# power_supply.net
KiCad netlist of a schematic drawn in EAGLE
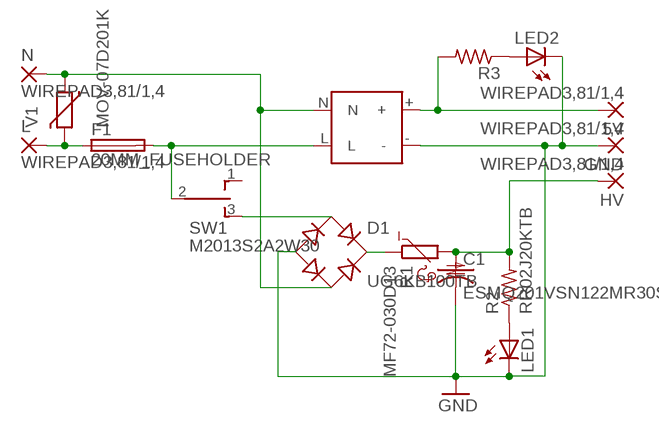
[diagram p0: schematic, sheet 1]

(export (version "E")
  (design (tool "Eeschema 10.0.6"))
  (components
    (comp (ref "5V")
      (value "WIREPAD3,81/1,4")
      (footprint "eagle-import:3,81_1,4")
      (libsource (lib "eagle-import") (part "WIREPAD3,81/1,4"))
    )
    (comp (ref "C1")
      (value "ESMQ201VSN122MR30S")
      (footprint "eagle-import:CAPPRD1000W200D3000H3000B")
      (libsource (lib "eagle-import") (part "ESMQ201VSN122MR30S"))
    )
    (comp (ref "D1")
      (value "UG6KB100TB")
      (footprint "eagle-import:UG6KB100TB")
      (libsource (lib "eagle-import") (part "UG6KB100TB"))
    )
    (comp (ref "F1")
      (value "20MM_FUSEHOLDER")
      (footprint "eagle-import:20MM_FUSEHOLDER")
      (libsource (lib "eagle-import") (part "20MM_FUSEHOLDER"))
    )
    (comp (ref "GND")
      (value "WIREPAD3,81/1,4")
      (footprint "eagle-import:3,81_1,4")
      (libsource (lib "eagle-import") (part "WIREPAD3,81/1,4"))
    )
    (comp (ref "HV")
      (value "WIREPAD3,81/1,4")
      (footprint "eagle-import:3,81_1,4")
      (libsource (lib "eagle-import") (part "WIREPAD3,81/1,4"))
    )
    (comp (ref "L")
      (value "WIREPAD3,81/1,4")
      (footprint "eagle-import:3,81_1,4")
      (libsource (lib "eagle-import") (part "WIREPAD3,81/1,4"))
    )
    (comp (ref "LED1")
      (value "LED5MM")
      (footprint "eagle-import:LED5MM")
      (libsource (lib "eagle-import") (part "LED5MM"))
    )
    (comp (ref "LED2")
      (value "LED5MM")
      (footprint "eagle-import:LED5MM")
      (libsource (lib "eagle-import") (part "LED5MM"))
    )
    (comp (ref "M1")
      (value "IRM-15-5")
      (footprint "eagle-import:IRM-15-5")
      (libsource (lib "eagle-import") (part "IRM-15-5"))
    )
    (comp (ref "N")
      (value "WIREPAD3,81/1,4")
      (footprint "eagle-import:3,81_1,4")
      (libsource (lib "eagle-import") (part "WIREPAD3,81/1,4"))
    )
    (comp (ref "R1")
      (value "MF72-030D13")
      (footprint "eagle-import:MF72-030D13")
      (libsource (lib "eagle-import") (part "MF72-030D13"))
    )
    (comp (ref "R2")
      (value "RR02J20KTB")
      (footprint "eagle-import:RESAD1360W80L900D350B")
      (libsource (lib "eagle-import") (part "RR02J20KTB"))
    )
    (comp (ref "R3")
      (value "R-US_0207/10")
      (footprint "eagle-import:0207_10")
      (libsource (lib "eagle-import") (part "R-US_0207/10"))
    )
    (comp (ref "SW1")
      (value "M2013S2A2W30")
      (footprint "eagle-import:M2013S2A2W30")
      (libsource (lib "eagle-import") (part "M2013S2A2W30"))
    )
    (comp (ref "V1")
      (value "MOV-07D201K")
      (footprint "eagle-import:MOV-07D201K")
      (libsource (lib "eagle-import") (part "MOV-07D201K"))
    )
  )
  (nets
    (net (code "1") (name "GND") (class "Default")
      (node (ref "C1") (pin "-") (pinfunction "2_-") (pintype "passive"))
      (node (ref "D1") (pin "-") (pinfunction "-_-") (pintype "passive"))
      (node (ref "GND") (pin "1") (pinfunction "P_1") (pintype "passive"))
      (node (ref "LED1") (pin "K") (pinfunction "C_K") (pintype "passive"))
      (node (ref "LED2") (pin "K") (pinfunction "C_K") (pintype "passive"))
      (node (ref "M1") (pin "-") (pinfunction "-_-") (pintype "bidirectional"))
    )
    (net (code "2") (name "Net-(5V-P)") (class "Default")
      (node (ref "5V") (pin "1") (pinfunction "P_1") (pintype "passive"))
      (node (ref "M1") (pin "+") (pinfunction "+_+") (pintype "bidirectional"))
      (node (ref "R3") (pin "2") (pinfunction "2_2") (pintype "passive"))
    )
    (net (code "3") (name "Net-(C1-1)") (class "Default")
      (node (ref "C1") (pin "+") (pinfunction "1_+") (pintype "passive"))
      (node (ref "HV") (pin "1") (pinfunction "P_1") (pintype "passive"))
      (node (ref "R1") (pin "P$2") (pinfunction "2_P$2") (pintype "passive"))
      (node (ref "R2") (pin "2") (pinfunction "2_2") (pintype "passive"))
    )
    (net (code "4") (name "Net-(D1-PadAC1)") (class "Default")
      (node (ref "D1") (pin "AC1") (pinfunction "AC1_AC1") (pintype "passive"))
      (node (ref "SW1") (pin "3") (pinfunction "3_3") (pintype "passive"))
    )
    (net (code "5") (name "Net-(F1-1)") (class "Default")
      (node (ref "F1") (pin "P$1") (pinfunction "1_P$1") (pintype "passive"))
      (node (ref "L") (pin "1") (pinfunction "P_1") (pintype "passive"))
      (node (ref "V1") (pin "P$2") (pinfunction "2_P$2") (pintype "passive"))
    )
    (net (code "6") (name "Net-(F1-2)") (class "Default")
      (node (ref "F1") (pin "P$2") (pinfunction "2_P$2") (pintype "passive"))
      (node (ref "M1") (pin "L") (pinfunction "L_L") (pintype "bidirectional"))
      (node (ref "SW1") (pin "2") (pinfunction "2_2") (pintype "passive"))
    )
    (net (code "7") (name "Net-(LED1-PadA)") (class "Default")
      (node (ref "LED1") (pin "A") (pinfunction "A_A") (pintype "passive"))
      (node (ref "R2") (pin "1") (pinfunction "1_1") (pintype "passive"))
    )
    (net (code "8") (name "Net-(LED2-PadA)") (class "Default")
      (node (ref "LED2") (pin "A") (pinfunction "A_A") (pintype "passive"))
      (node (ref "R3") (pin "1") (pinfunction "1_1") (pintype "passive"))
    )
    (net (code "9") (name "Net-(N-P)") (class "Default")
      (node (ref "D1") (pin "AC2") (pinfunction "AC2_AC2") (pintype "passive"))
      (node (ref "M1") (pin "N") (pinfunction "N_N") (pintype "bidirectional"))
      (node (ref "N") (pin "1") (pinfunction "P_1") (pintype "passive"))
      (node (ref "V1") (pin "P$1") (pinfunction "1_P$1") (pintype "passive"))
    )
    (net (code "10") (name "Net-(R1-1)") (class "Default")
      (node (ref "D1") (pin "+") (pinfunction "+_+") (pintype "passive"))
      (node (ref "R1") (pin "P$1") (pinfunction "1_P$1") (pintype "passive"))
    )
    (net (code "11") (name "unconnected-(SW1-Pad1)") (class "Default")
      (node (ref "SW1") (pin "1") (pinfunction "1_1") (pintype "passive"))
    )
  )
)
